# 8_USB_power_Data.net
KiCad netlist of a schematic drawn in Altium Designer
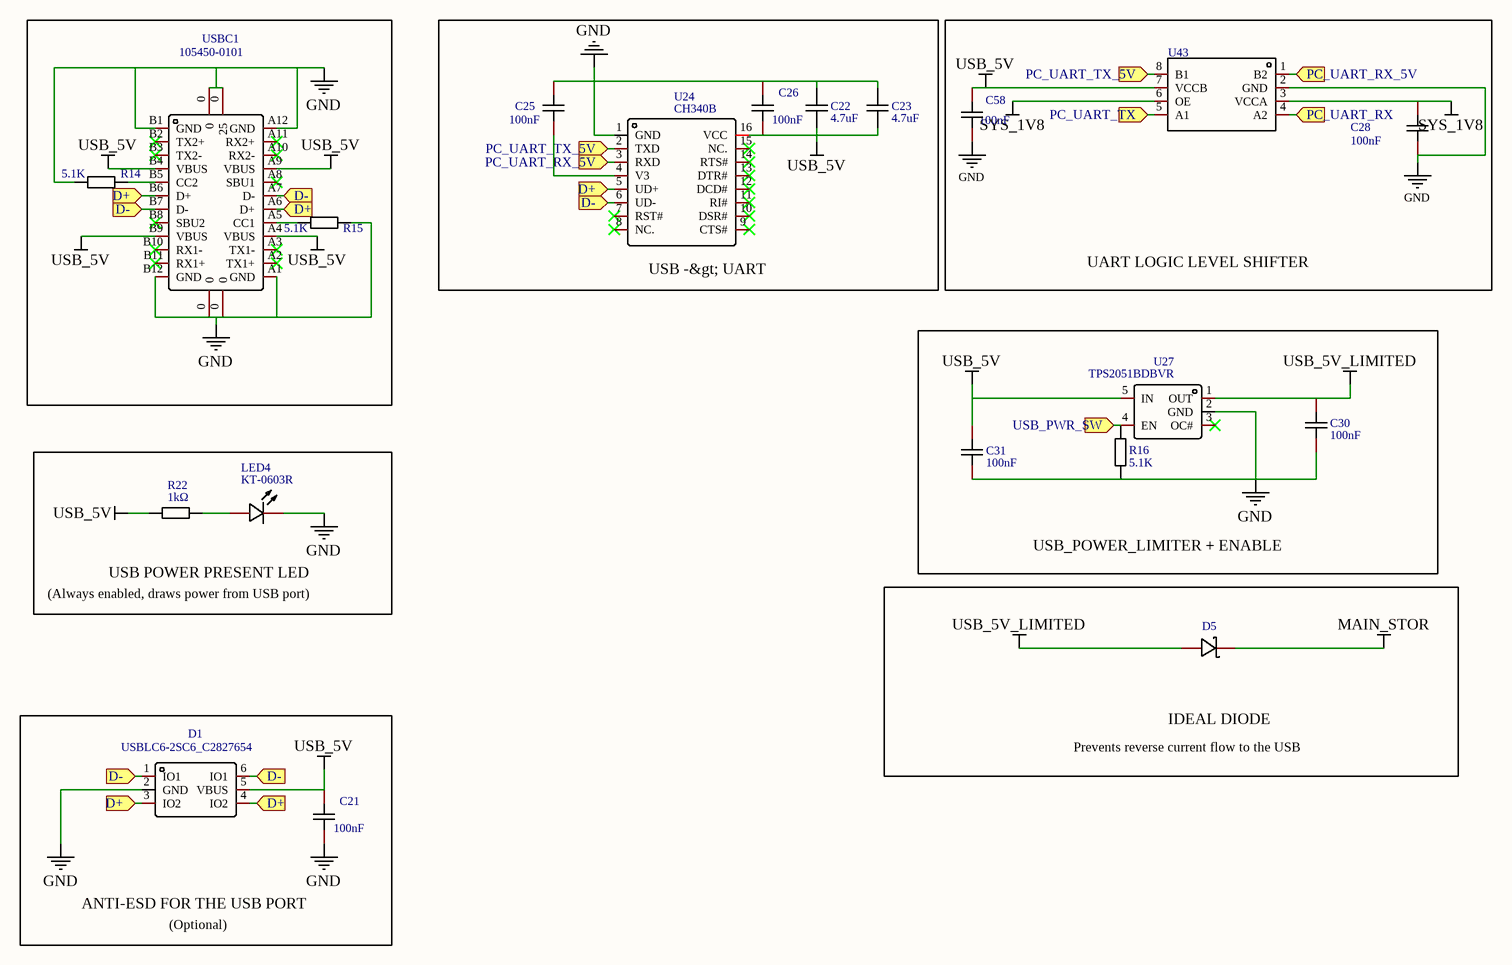
[diagram p0: 8_USB power + Data.schdoc]

(export (version "E")
  (design (tool "Eeschema 10.0.6"))
  (components
    (comp (ref "C21")
      (value "100nF")
      (fields
        (field (name "NAME") "100nF")
        (field (name "MANUFACTURER") "YAGEO")
        (field (name "MANUFACTURER PART") "CC0603KRX7R9BB104")
      )
      (libsource (lib "altium-import") (part "root_1_CC0603KRX7R9BB104_"))
    )
    (comp (ref "C22")
      (value "4.7uF")
      (fields
        (field (name "NAME") "4.7uF")
        (field (name "MANUFACTURER PART") "CL10A475KO8NNNC")
        (field (name "MANUFACTURER") "SAMSUNG")
      )
      (libsource (lib "altium-import") (part "root_1_CL10A475KO8NNNC_"))
    )
    (comp (ref "C23")
      (value "4.7uF")
      (fields
        (field (name "NAME") "4.7uF")
        (field (name "MANUFACTURER PART") "CL10A475KO8NNNC")
        (field (name "MANUFACTURER") "SAMSUNG")
      )
      (libsource (lib "altium-import") (part "root_1_CL10A475KO8NNNC_"))
    )
    (comp (ref "C25")
      (value "100nF")
      (fields
        (field (name "NAME") "100nF")
        (field (name "MANUFACTURER") "YAGEO")
        (field (name "MANUFACTURER PART") "CC0603KRX7R9BB104")
      )
      (libsource (lib "altium-import") (part "root_1_CC0603KRX7R9BB104_"))
    )
    (comp (ref "C26")
      (value "100nF")
      (fields
        (field (name "NAME") "100nF")
        (field (name "MANUFACTURER") "YAGEO")
        (field (name "MANUFACTURER PART") "CC0603KRX7R9BB104")
      )
      (libsource (lib "altium-import") (part "root_1_CC0603KRX7R9BB104_"))
    )
    (comp (ref "C28")
      (value "100nF")
      (fields
        (field (name "NAME") "100nF")
        (field (name "MANUFACTURER") "YAGEO")
        (field (name "MANUFACTURER PART") "CC0603KRX7R9BB104")
      )
      (libsource (lib "altium-import") (part "root_3_CC0603KRX7R9BB104_"))
    )
    (comp (ref "C30")
      (value "100nF")
      (fields
        (field (name "NAME") "100nF")
        (field (name "MANUFACTURER") "YAGEO")
        (field (name "MANUFACTURER PART") "CC0603KRX7R9BB104")
      )
      (libsource (lib "altium-import") (part "root_3_CC0603KRX7R9BB104_"))
    )
    (comp (ref "C31")
      (value "100nF")
      (fields
        (field (name "NAME") "100nF")
        (field (name "MANUFACTURER") "YAGEO")
        (field (name "MANUFACTURER PART") "CC0603KRX7R9BB104")
      )
      (libsource (lib "altium-import") (part "root_3_CC0603KRX7R9BB104_"))
    )
    (comp (ref "C58")
      (value "100nF")
      (fields
        (field (name "NAME") "100nF")
        (field (name "MANUFACTURER") "YAGEO")
        (field (name "MANUFACTURER PART") "CC0603KRX7R9BB104")
      )
      (libsource (lib "altium-import") (part "root_3_CC0603KRX7R9BB104_"))
    )
    (comp (ref "D1")
      (value "USBLC6-2SC6_C2827654")
      (fields
        (field (name "NAME") "USBLC6-2SC6_C2827654")
        (field (name "MANUFACTURER") "TECH PUBLIC(台舟电子)")
        (field (name "MANUFACTURER PART") "USBLC6-2SC6")
      )
      (libsource (lib "altium-import") (part "root_0_USBLC6-2SC6_"))
    )
    (comp (ref "D5")
      (value "SS54")
      (description "Reverse Voltage (Vr):40V Average Rectified Current (Io):5A Forward Voltage (Vf@If):550mV@5A")
      (fields (field (name "MANUFACTURER") "MDD"))
      (libsource (lib "altium-import") (part "root_2_SS54_"))
    )
    (comp (ref "LED4")
      (value "KT-0603R")
      (fields (field (name "NAME") "KT-0603R") (field (name "MANUFACTURER") "KENTO"))
      (libsource (lib "altium-import") (part "root_2_KT-0603R_"))
    )
    (comp (ref "R14")
      (value "5.1K")
      (fields
        (field (name "NAME") "5.1K")
        (field (name "MANUFACTURER PART") "0603WAF5101T5E")
        (field (name "MANUFACTURER") "UniOhm")
      )
      (libsource (lib "altium-import") (part "root_0_0603WAF5101T5E_"))
    )
    (comp (ref "R15")
      (value "5.1K")
      (fields
        (field (name "NAME") "5.1K")
        (field (name "MANUFACTURER PART") "0603WAF5101T5E")
        (field (name "MANUFACTURER") "UniOhm")
      )
      (libsource (lib "altium-import") (part "root_0_0603WAF5101T5E_"))
    )
    (comp (ref "R16")
      (value "5.1K")
      (fields
        (field (name "NAME") "5.1K")
        (field (name "MANUFACTURER PART") "0603WAF5101T5E")
        (field (name "MANUFACTURER") "UniOhm")
      )
      (libsource (lib "altium-import") (part "root_1_0603WAF5101T5E_"))
    )
    (comp (ref "R22")
      (value "1kΩ")
      (fields
        (field (name "NAME") "1kΩ")
        (field (name "MANUFACTURER") "UniOhm")
        (field (name "MANUFACTURER PART") "0603WAF1001T5E")
      )
      (libsource (lib "altium-import") (part "root_0_0603WAF1001T5E_"))
    )
    (comp (ref "U24")
      (value "CH340B")
      (fields (field (name "NAME") "CH340B") (field (name "MANUFACTURER") "WCH"))
      (libsource (lib "altium-import") (part "root_0_CH340B_"))
    )
    (comp (ref "U27")
      (value "TPS2051BDBVR")
      (fields (field (name "NAME") "TPS2051BDBVR") (field (name "MANUFACTURER") "TI"))
      (libsource (lib "altium-import") (part "root_0_TPS2051BDBVR_"))
    )
    (comp (ref "U43")
      (value "TXS0102DCUR")
      (fields (field (name "MANUFACTURER") "TI(德州仪器)"))
      (libsource (lib "altium-import") (part "root_0_mirrored_TXS0102DCUR_"))
    )
    (comp (ref "USBC1")
      (value "105450-0101")
      (fields (field (name "NAME") "105450-0101") (field (name "MANUFACTURER") "MOLEX"))
      (libsource (lib "altium-import") (part "root_0_105450-0101_"))
    )
  )
  (nets
    (net (code "1") (name "/D+") (class "Default")
      (node (ref "D1") (pin "3") (pinfunction "IO2_3") (pintype "passive"))
      (node (ref "D1") (pin "4") (pinfunction "IO2_4") (pintype "passive"))
      (node (ref "U24") (pin "5") (pinfunction "UD+_5") (pintype "passive"))
      (node (ref "USBC1") (pin "A6") (pinfunction "D+_A6") (pintype "passive"))
      (node (ref "USBC1") (pin "B6") (pinfunction "D+_B6") (pintype "passive"))
    )
    (net (code "2") (name "/D-") (class "Default")
      (node (ref "D1") (pin "1") (pinfunction "IO1_1") (pintype "passive"))
      (node (ref "D1") (pin "6") (pinfunction "IO1_6") (pintype "passive"))
      (node (ref "U24") (pin "6") (pinfunction "UD-_6") (pintype "passive"))
      (node (ref "USBC1") (pin "A7") (pinfunction "D-_A7") (pintype "passive"))
      (node (ref "USBC1") (pin "B7") (pinfunction "D-_B7") (pintype "passive"))
    )
    (net (code "3") (name "/PC_UART_RX") (class "Default")
      (node (ref "U43") (pin "4") (pinfunction "A2_4") (pintype "passive"))
    )
    (net (code "4") (name "/PC_UART_RX_5V") (class "Default")
      (node (ref "U24") (pin "3") (pinfunction "RXD_3") (pintype "passive"))
      (node (ref "U43") (pin "1") (pinfunction "B2_1") (pintype "passive"))
    )
    (net (code "5") (name "/PC_UART_TX") (class "Default")
      (node (ref "U43") (pin "5") (pinfunction "A1_5") (pintype "passive"))
    )
    (net (code "6") (name "/PC_UART_TX_5V") (class "Default")
      (node (ref "U24") (pin "2") (pinfunction "TXD_2") (pintype "passive"))
      (node (ref "U43") (pin "8") (pinfunction "B1_8") (pintype "passive"))
    )
    (net (code "7") (name "/USB_PWR_SW") (class "Default")
      (node (ref "R16") (pin "2") (pinfunction "2_2") (pintype "passive"))
      (node (ref "U27") (pin "4") (pinfunction "EN_4") (pintype "passive"))
    )
    (net (code "8") (name "GND") (class "Default")
      (node (ref "C21") (pin "1") (pinfunction "1_1") (pintype "passive"))
      (node (ref "C22") (pin "2") (pinfunction "2_2") (pintype "passive"))
      (node (ref "C23") (pin "2") (pinfunction "2_2") (pintype "passive"))
      (node (ref "C25") (pin "2") (pinfunction "2_2") (pintype "passive"))
      (node (ref "C26") (pin "2") (pinfunction "2_2") (pintype "passive"))
      (node (ref "C28") (pin "2") (pinfunction "2_2") (pintype "passive"))
      (node (ref "C30") (pin "2") (pinfunction "2_2") (pintype "passive"))
      (node (ref "C31") (pin "2") (pinfunction "2_2") (pintype "passive"))
      (node (ref "C58") (pin "2") (pinfunction "2_2") (pintype "passive"))
      (node (ref "D1") (pin "2") (pinfunction "GND_2") (pintype "passive"))
      (node (ref "LED4") (pin "2") (pinfunction "K_2") (pintype "passive"))
      (node (ref "R14") (pin "1") (pinfunction "1_1") (pintype "passive"))
      (node (ref "R15") (pin "2") (pinfunction "2_2") (pintype "passive"))
      (node (ref "R16") (pin "1") (pinfunction "1_1") (pintype "passive"))
      (node (ref "U24") (pin "1") (pinfunction "GND_1") (pintype "passive"))
      (node (ref "U27") (pin "2") (pinfunction "GND_2") (pintype "passive"))
      (node (ref "U43") (pin "2") (pinfunction "GND_2") (pintype "passive"))
      (node (ref "USBC1") (pin "0") (pinfunction "0_0") (pintype "passive"))
      (node (ref "USBC1") (pin "A1") (pinfunction "GND_A1") (pintype "passive"))
      (node (ref "USBC1") (pin "A12") (pinfunction "GND_A12") (pintype "passive"))
      (node (ref "USBC1") (pin "B1") (pinfunction "GND_B1") (pintype "passive"))
      (node (ref "USBC1") (pin "B12") (pinfunction "GND_B12") (pintype "passive"))
    )
    (net (code "9") (name "MAIN_STOR") (class "Default")
      (node (ref "D5") (pin "2") (pinfunction "K_2") (pintype "passive"))
    )
    (net (code "10") (name "Net-(LED4-A)") (class "Default")
      (node (ref "LED4") (pin "1") (pinfunction "A_1") (pintype "passive"))
      (node (ref "R22") (pin "2") (pinfunction "2_2") (pintype "passive"))
    )
    (net (code "11") (name "Net-(U24-V3)") (class "Default")
      (node (ref "C25") (pin "1") (pinfunction "1_1") (pintype "passive"))
      (node (ref "U24") (pin "4") (pinfunction "V3_4") (pintype "passive"))
    )
    (net (code "12") (name "Net-(USBC1-CC1)") (class "Default")
      (node (ref "R15") (pin "1") (pinfunction "1_1") (pintype "passive"))
      (node (ref "USBC1") (pin "A5") (pinfunction "CC1_A5") (pintype "passive"))
    )
    (net (code "13") (name "Net-(USBC1-CC2)") (class "Default")
      (node (ref "R14") (pin "2") (pinfunction "2_2") (pintype "passive"))
      (node (ref "USBC1") (pin "B5") (pinfunction "CC2_B5") (pintype "passive"))
    )
    (net (code "14") (name "SYS_1V8") (class "Default")
      (node (ref "C28") (pin "1") (pinfunction "1_1") (pintype "passive"))
      (node (ref "U43") (pin "3") (pinfunction "VCCA_3") (pintype "passive"))
      (node (ref "U43") (pin "6") (pinfunction "OE_6") (pintype "passive"))
    )
    (net (code "15") (name "USB_5V") (class "Default")
      (node (ref "C21") (pin "2") (pinfunction "2_2") (pintype "passive"))
      (node (ref "C22") (pin "1") (pinfunction "1_1") (pintype "passive"))
      (node (ref "C23") (pin "1") (pinfunction "1_1") (pintype "passive"))
      (node (ref "C26") (pin "1") (pinfunction "1_1") (pintype "passive"))
      (node (ref "C31") (pin "1") (pinfunction "1_1") (pintype "passive"))
      (node (ref "C58") (pin "1") (pinfunction "1_1") (pintype "passive"))
      (node (ref "D1") (pin "5") (pinfunction "VBUS_5") (pintype "passive"))
      (node (ref "R22") (pin "1") (pinfunction "1_1") (pintype "passive"))
      (node (ref "U24") (pin "16") (pinfunction "VCC_16") (pintype "passive"))
      (node (ref "U27") (pin "5") (pinfunction "IN_5") (pintype "passive"))
      (node (ref "U43") (pin "7") (pinfunction "VCCB_7") (pintype "passive"))
      (node (ref "USBC1") (pin "A4") (pinfunction "VBUS_A4") (pintype "passive"))
      (node (ref "USBC1") (pin "A9") (pinfunction "VBUS_A9") (pintype "passive"))
      (node (ref "USBC1") (pin "B4") (pinfunction "VBUS_B4") (pintype "passive"))
      (node (ref "USBC1") (pin "B9") (pinfunction "VBUS_B9") (pintype "passive"))
    )
    (net (code "16") (name "USB_5V_LIMITED") (class "Default")
      (node (ref "C30") (pin "1") (pinfunction "1_1") (pintype "passive"))
      (node (ref "D5") (pin "1") (pinfunction "A_1") (pintype "passive"))
      (node (ref "U27") (pin "1") (pinfunction "OUT_1") (pintype "passive"))
    )
    (net (code "17") (name "unconnected-(U24-CTS#-Pad9)") (class "Default")
      (node (ref "U24") (pin "9") (pinfunction "CTS#_9") (pintype "passive+no_connect"))
    )
    (net (code "18") (name "unconnected-(U24-DCD#-Pad12)") (class "Default")
      (node (ref "U24") (pin "12") (pinfunction "DCD#_12") (pintype "passive+no_connect"))
    )
    (net (code "19") (name "unconnected-(U24-DSR#-Pad10)") (class "Default")
      (node (ref "U24") (pin "10") (pinfunction "DSR#_10") (pintype "passive+no_connect"))
    )
    (net (code "20") (name "unconnected-(U24-DTR#-Pad13)") (class "Default")
      (node (ref "U24") (pin "13") (pinfunction "DTR#_13") (pintype "passive+no_connect"))
    )
    (net (code "21") (name "unconnected-(U24-NC.-Pad8)") (class "Default")
      (node (ref "U24") (pin "8") (pinfunction "NC._8") (pintype "passive+no_connect"))
    )
    (net (code "22") (name "unconnected-(U24-NC.-Pad15)") (class "Default")
      (node (ref "U24") (pin "15") (pinfunction "NC._15") (pintype "passive+no_connect"))
    )
    (net (code "23") (name "unconnected-(U24-RI#-Pad11)") (class "Default")
      (node (ref "U24") (pin "11") (pinfunction "RI#_11") (pintype "passive+no_connect"))
    )
    (net (code "24") (name "unconnected-(U24-RST#-Pad7)") (class "Default")
      (node (ref "U24") (pin "7") (pinfunction "RST#_7") (pintype "passive+no_connect"))
    )
    (net (code "25") (name "unconnected-(U24-RTS#-Pad14)") (class "Default")
      (node (ref "U24") (pin "14") (pinfunction "RTS#_14") (pintype "passive+no_connect"))
    )
    (net (code "26") (name "unconnected-(U27-OC#-Pad3)") (class "Default")
      (node (ref "U27") (pin "3") (pinfunction "OC#_3") (pintype "passive+no_connect"))
    )
    (net (code "27") (name "unconnected-(USBC1-RX1+-PadB11)") (class "Default")
      (node (ref "USBC1") (pin "B11") (pinfunction "RX1+_B11") (pintype "passive+no_connect"))
    )
    (net (code "28") (name "unconnected-(USBC1-RX1--PadB10)") (class "Default")
      (node (ref "USBC1") (pin "B10") (pinfunction "RX1-_B10") (pintype "passive+no_connect"))
    )
    (net (code "29") (name "unconnected-(USBC1-RX2+-PadA11)") (class "Default")
      (node (ref "USBC1") (pin "A11") (pinfunction "RX2+_A11") (pintype "passive+no_connect"))
    )
    (net (code "30") (name "unconnected-(USBC1-RX2--PadA10)") (class "Default")
      (node (ref "USBC1") (pin "A10") (pinfunction "RX2-_A10") (pintype "passive+no_connect"))
    )
    (net (code "31") (name "unconnected-(USBC1-SBU1-PadA8)") (class "Default")
      (node (ref "USBC1") (pin "A8") (pinfunction "SBU1_A8") (pintype "passive+no_connect"))
    )
    (net (code "32") (name "unconnected-(USBC1-SBU2-PadB8)") (class "Default")
      (node (ref "USBC1") (pin "B8") (pinfunction "SBU2_B8") (pintype "passive+no_connect"))
    )
    (net (code "33") (name "unconnected-(USBC1-TX1+-PadA2)") (class "Default")
      (node (ref "USBC1") (pin "A2") (pinfunction "TX1+_A2") (pintype "passive+no_connect"))
    )
    (net (code "34") (name "unconnected-(USBC1-TX1--PadA3)") (class "Default")
      (node (ref "USBC1") (pin "A3") (pinfunction "TX1-_A3") (pintype "passive+no_connect"))
    )
    (net (code "35") (name "unconnected-(USBC1-TX2+-PadB2)") (class "Default")
      (node (ref "USBC1") (pin "B2") (pinfunction "TX2+_B2") (pintype "passive+no_connect"))
    )
    (net (code "36") (name "unconnected-(USBC1-TX2--PadB3)") (class "Default")
      (node (ref "USBC1") (pin "B3") (pinfunction "TX2-_B3") (pintype "passive+no_connect"))
    )
  )
)
